# ROTARY_SW.net
KiCad netlist of a schematic drawn in Altium Designer
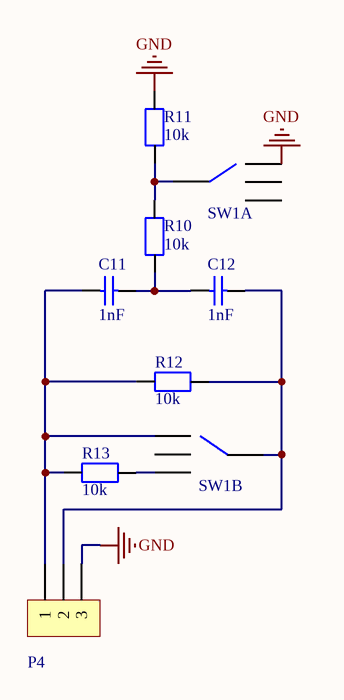
[diagram p0: ROTARY_SW.SchDoc]

(export (version "E")
  (design (tool "Eeschema 10.0.6"))
  (components
    (comp (ref "C11")
      (value "1nF")
      (footprint "0805_Capacitor")
      (fields (field (name "Comment") "Capacitor"))
      (libsource (lib "SchLib1") (part "Capacitor"))
    )
    (comp (ref "C12")
      (value "1nF")
      (footprint "0805_Capacitor")
      (fields (field (name "Comment") "Capacitor"))
      (libsource (lib "SchLib1") (part "Capacitor"))
    )
    (comp (ref "P4")
      (value "SIL-CONN-3")
      (footprint "SIL-CONN-3-R1")
      (libsource (lib "SchLib1") (part "SIL-CONN-3"))
    )
    (comp (ref "R10")
      (value "10k")
      (footprint "0805_Resistor")
      (fields (field (name "Comment") "Resistor"))
      (libsource (lib "") (part "Resistor_1"))
    )
    (comp (ref "R11")
      (value "10k")
      (footprint "0805_Resistor")
      (fields (field (name "Comment") "Resistor"))
      (libsource (lib "") (part "Resistor_1"))
    )
    (comp (ref "R12")
      (value "10k")
      (footprint "0805_Resistor")
      (fields (field (name "Comment") "Resistor"))
      (libsource (lib "SchLib1") (part "Resistor"))
    )
    (comp (ref "R13")
      (value "10k")
      (footprint "0805_Resistor")
      (fields (field (name "Comment") "Resistor"))
      (libsource (lib "SchLib1") (part "Resistor"))
    )
    (comp (ref "SW1")
      (value "SRBM131400")
      (footprint "SRBM131400")
      (libsource (lib "SchLib1") (part "SRBM131400"))
    )
  )
  (nets
    (net (code "1") (name "GND") (class "Default")
      (node (ref "P4") (pin "3") (pinfunction "3_3") (pintype "passive"))
      (node (ref "R11") (pin "2") (pinfunction "2_2") (pintype "passive"))
      (node (ref "SW1") (pin "2") (pinfunction "2_2") (pintype "passive"))
    )
    (net (code "2") (name "Net-(C11-Pad1)") (class "Default")
      (node (ref "C11") (pin "1") (pinfunction "1_1") (pintype "passive"))
      (node (ref "P4") (pin "1") (pinfunction "1_1") (pintype "passive"))
      (node (ref "R12") (pin "2") (pinfunction "2_2") (pintype "passive"))
      (node (ref "R13") (pin "2") (pinfunction "2_2") (pintype "passive"))
      (node (ref "SW1") (pin "6") (pinfunction "6_6") (pintype "passive"))
    )
    (net (code "3") (name "Net-(C11-Pad2)") (class "Default")
      (node (ref "C11") (pin "2") (pinfunction "2_2") (pintype "passive"))
      (node (ref "C12") (pin "1") (pinfunction "1_1") (pintype "passive"))
      (node (ref "R10") (pin "1") (pinfunction "1_1") (pintype "passive"))
    )
    (net (code "4") (name "Net-(C12-Pad2)") (class "Default")
      (node (ref "C12") (pin "2") (pinfunction "2_2") (pintype "passive"))
      (node (ref "P4") (pin "2") (pinfunction "2_2") (pintype "passive"))
      (node (ref "R12") (pin "1") (pinfunction "1_1") (pintype "passive"))
      (node (ref "SW1") (pin "10") (pinfunction "10_10") (pintype "passive"))
    )
    (net (code "5") (name "Net-(R10-Pad2)") (class "Default")
      (node (ref "R10") (pin "2") (pinfunction "2_2") (pintype "passive"))
      (node (ref "R11") (pin "1") (pinfunction "1_1") (pintype "passive"))
      (node (ref "SW1") (pin "1") (pinfunction "1_1") (pintype "passive"))
    )
    (net (code "6") (name "Net-(R13-Pad1)") (class "Default")
      (node (ref "R13") (pin "1") (pinfunction "1_1") (pintype "passive"))
      (node (ref "SW1") (pin "8") (pinfunction "8_8") (pintype "passive"))
    )
    (net (code "7") (name "unconnected-(SW1-Pad3)") (class "Default")
      (node (ref "SW1") (pin "3") (pinfunction "3_3") (pintype "passive"))
    )
    (net (code "8") (name "unconnected-(SW1-Pad4)") (class "Default")
      (node (ref "SW1") (pin "4") (pinfunction "4_4") (pintype "passive"))
    )
    (net (code "9") (name "unconnected-(SW1-Pad7)") (class "Default")
      (node (ref "SW1") (pin "7") (pinfunction "7_7") (pintype "passive"))
    )
  )
)
